# arduinoRGBkaleidoscopeCkt1_v2.net
KiCad netlist of a schematic drawn in EAGLE
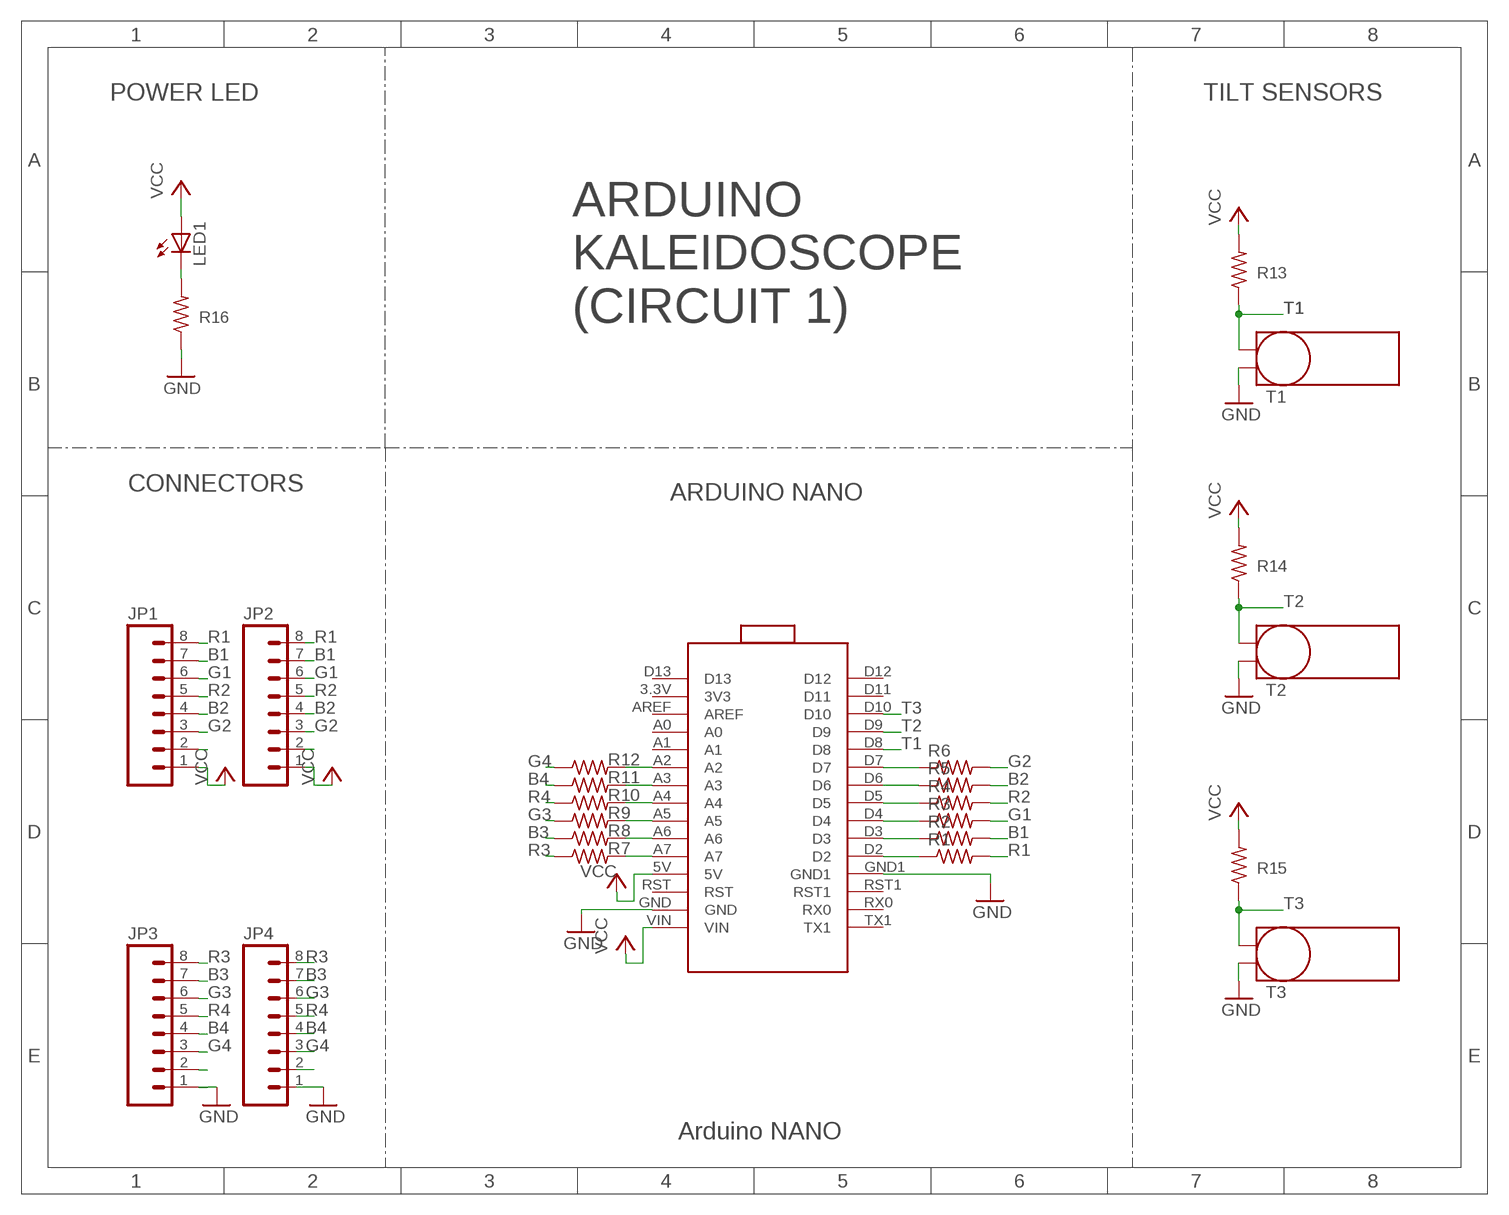
[diagram p0: schematic, sheet 1]

(export (version "E")
  (design (tool "Eeschema 10.0.6"))
  (components
    (comp (ref "JP1")
      (value "M081X08")
      (footprint "eagle-import:1X08")
      (libsource (lib "eagle-import") (part "M081X08"))
    )
    (comp (ref "JP2")
      (value "M081X08")
      (footprint "eagle-import:1X08")
      (libsource (lib "eagle-import") (part "M081X08"))
    )
    (comp (ref "JP3")
      (value "M081X08")
      (footprint "eagle-import:1X08")
      (libsource (lib "eagle-import") (part "M081X08"))
    )
    (comp (ref "JP4")
      (value "M081X08")
      (footprint "eagle-import:1X08")
      (libsource (lib "eagle-import") (part "M081X08"))
    )
    (comp (ref "LED1")
      (value "LED3MM")
      (footprint "eagle-import:LED3MM")
      (libsource (lib "eagle-import") (part "LED3MM"))
    )
    (comp (ref "R1")
      (value "RESISTOR0805")
      (footprint "eagle-import:R0805")
      (libsource (lib "eagle-import") (part "RESISTOR0805"))
    )
    (comp (ref "R2")
      (value "RESISTOR0805")
      (footprint "eagle-import:R0805")
      (libsource (lib "eagle-import") (part "RESISTOR0805"))
    )
    (comp (ref "R3")
      (value "RESISTOR0805")
      (footprint "eagle-import:R0805")
      (libsource (lib "eagle-import") (part "RESISTOR0805"))
    )
    (comp (ref "R4")
      (value "RESISTOR0805")
      (footprint "eagle-import:R0805")
      (libsource (lib "eagle-import") (part "RESISTOR0805"))
    )
    (comp (ref "R5")
      (value "RESISTOR0805")
      (footprint "eagle-import:R0805")
      (libsource (lib "eagle-import") (part "RESISTOR0805"))
    )
    (comp (ref "R6")
      (value "RESISTOR0805")
      (footprint "eagle-import:R0805")
      (libsource (lib "eagle-import") (part "RESISTOR0805"))
    )
    (comp (ref "R7")
      (value "RESISTOR0805")
      (footprint "eagle-import:R0805")
      (libsource (lib "eagle-import") (part "RESISTOR0805"))
    )
    (comp (ref "R8")
      (value "RESISTOR0805")
      (footprint "eagle-import:R0805")
      (libsource (lib "eagle-import") (part "RESISTOR0805"))
    )
    (comp (ref "R9")
      (value "RESISTOR0805")
      (footprint "eagle-import:R0805")
      (libsource (lib "eagle-import") (part "RESISTOR0805"))
    )
    (comp (ref "R10")
      (value "RESISTOR0805")
      (footprint "eagle-import:R0805")
      (libsource (lib "eagle-import") (part "RESISTOR0805"))
    )
    (comp (ref "R11")
      (value "RESISTOR0805")
      (footprint "eagle-import:R0805")
      (libsource (lib "eagle-import") (part "RESISTOR0805"))
    )
    (comp (ref "R12")
      (value "RESISTOR0805")
      (footprint "eagle-import:R0805")
      (libsource (lib "eagle-import") (part "RESISTOR0805"))
    )
    (comp (ref "R13")
      (value "R-US_0204/7")
      (footprint "eagle-import:0204_7")
      (libsource (lib "eagle-import") (part "R-US_0204/7"))
    )
    (comp (ref "R14")
      (value "R-US_0204/7")
      (footprint "eagle-import:0204_7")
      (libsource (lib "eagle-import") (part "R-US_0204/7"))
    )
    (comp (ref "R15")
      (value "R-US_0204/7")
      (footprint "eagle-import:0204_7")
      (libsource (lib "eagle-import") (part "R-US_0204/7"))
    )
    (comp (ref "R16")
      (value "R-US_0204/7")
      (footprint "eagle-import:0204_7")
      (libsource (lib "eagle-import") (part "R-US_0204/7"))
    )
    (comp (ref "T1")
      (value "TILTSENSORE2.5-7")
      (footprint "eagle-import:TILTSENSOR")
      (libsource (lib "eagle-import") (part "TILTSENSORE2.5-7"))
    )
    (comp (ref "T2")
      (value "TILTSENSORE2.5-7")
      (footprint "eagle-import:TILTSENSOR")
      (libsource (lib "eagle-import") (part "TILTSENSORE2.5-7"))
    )
    (comp (ref "T3")
      (value "TILTSENSORE2.5-7")
      (footprint "eagle-import:TILTSENSOR")
      (libsource (lib "eagle-import") (part "TILTSENSORE2.5-7"))
    )
    (comp (ref "U$2")
      (value "NANO")
      (footprint "eagle-import:NANO-2")
      (libsource (lib "eagle-import") (part "NANO"))
    )
  )
  (nets
    (net (code "1") (name "/B1") (class "Default")
      (node (ref "JP1") (pin "7") (pinfunction "7_7") (pintype "passive"))
      (node (ref "JP2") (pin "7") (pinfunction "7_7") (pintype "passive"))
      (node (ref "R2") (pin "2") (pinfunction "2_2") (pintype "passive"))
    )
    (net (code "2") (name "/B2") (class "Default")
      (node (ref "JP1") (pin "4") (pinfunction "4_4") (pintype "passive"))
      (node (ref "JP2") (pin "4") (pinfunction "4_4") (pintype "passive"))
      (node (ref "R5") (pin "2") (pinfunction "2_2") (pintype "passive"))
    )
    (net (code "3") (name "/B3") (class "Default")
      (node (ref "JP3") (pin "7") (pinfunction "7_7") (pintype "passive"))
      (node (ref "JP4") (pin "7") (pinfunction "7_7") (pintype "passive"))
      (node (ref "R8") (pin "1") (pinfunction "1_1") (pintype "passive"))
    )
    (net (code "4") (name "/B4") (class "Default")
      (node (ref "JP3") (pin "4") (pinfunction "4_4") (pintype "passive"))
      (node (ref "JP4") (pin "4") (pinfunction "4_4") (pintype "passive"))
      (node (ref "R11") (pin "1") (pinfunction "1_1") (pintype "passive"))
    )
    (net (code "5") (name "/G1") (class "Default")
      (node (ref "JP1") (pin "6") (pinfunction "6_6") (pintype "passive"))
      (node (ref "JP2") (pin "6") (pinfunction "6_6") (pintype "passive"))
      (node (ref "R3") (pin "2") (pinfunction "2_2") (pintype "passive"))
    )
    (net (code "6") (name "/G2") (class "Default")
      (node (ref "JP1") (pin "3") (pinfunction "3_3") (pintype "passive"))
      (node (ref "JP2") (pin "3") (pinfunction "3_3") (pintype "passive"))
      (node (ref "R6") (pin "2") (pinfunction "2_2") (pintype "passive"))
    )
    (net (code "7") (name "/G3") (class "Default")
      (node (ref "JP3") (pin "6") (pinfunction "6_6") (pintype "passive"))
      (node (ref "JP4") (pin "6") (pinfunction "6_6") (pintype "passive"))
      (node (ref "R9") (pin "1") (pinfunction "1_1") (pintype "passive"))
    )
    (net (code "8") (name "/G4") (class "Default")
      (node (ref "JP3") (pin "3") (pinfunction "3_3") (pintype "passive"))
      (node (ref "JP4") (pin "3") (pinfunction "3_3") (pintype "passive"))
      (node (ref "R12") (pin "1") (pinfunction "1_1") (pintype "passive"))
    )
    (net (code "9") (name "/R1") (class "Default")
      (node (ref "JP1") (pin "8") (pinfunction "8_8") (pintype "passive"))
      (node (ref "JP2") (pin "8") (pinfunction "8_8") (pintype "passive"))
      (node (ref "R1") (pin "2") (pinfunction "2_2") (pintype "passive"))
    )
    (net (code "10") (name "/R2") (class "Default")
      (node (ref "JP1") (pin "5") (pinfunction "5_5") (pintype "passive"))
      (node (ref "JP2") (pin "5") (pinfunction "5_5") (pintype "passive"))
      (node (ref "R4") (pin "2") (pinfunction "2_2") (pintype "passive"))
    )
    (net (code "11") (name "/R3") (class "Default")
      (node (ref "JP3") (pin "8") (pinfunction "8_8") (pintype "passive"))
      (node (ref "JP4") (pin "8") (pinfunction "8_8") (pintype "passive"))
      (node (ref "R7") (pin "1") (pinfunction "1_1") (pintype "passive"))
    )
    (net (code "12") (name "/R4") (class "Default")
      (node (ref "JP3") (pin "5") (pinfunction "5_5") (pintype "passive"))
      (node (ref "JP4") (pin "5") (pinfunction "5_5") (pintype "passive"))
      (node (ref "R10") (pin "1") (pinfunction "1_1") (pintype "passive"))
    )
    (net (code "13") (name "/T1") (class "Default")
      (node (ref "R13") (pin "1") (pinfunction "1_1") (pintype "passive"))
      (node (ref "T1") (pin "+") (pinfunction "+_+") (pintype "passive"))
      (node (ref "U$2") (pin "D8") (pinfunction "D8_D8") (pintype "bidirectional"))
    )
    (net (code "14") (name "/T2") (class "Default")
      (node (ref "R14") (pin "1") (pinfunction "1_1") (pintype "passive"))
      (node (ref "T2") (pin "+") (pinfunction "+_+") (pintype "passive"))
      (node (ref "U$2") (pin "D9") (pinfunction "D9_D9") (pintype "bidirectional"))
    )
    (net (code "15") (name "/T3") (class "Default")
      (node (ref "R15") (pin "1") (pinfunction "1_1") (pintype "passive"))
      (node (ref "T3") (pin "+") (pinfunction "+_+") (pintype "passive"))
      (node (ref "U$2") (pin "D10") (pinfunction "D10_D10") (pintype "bidirectional"))
    )
    (net (code "16") (name "GND") (class "Default")
      (node (ref "JP3") (pin "1") (pinfunction "1_1") (pintype "passive"))
      (node (ref "JP4") (pin "1") (pinfunction "1_1") (pintype "passive"))
      (node (ref "R16") (pin "1") (pinfunction "1_1") (pintype "passive"))
      (node (ref "T1") (pin "-") (pinfunction "-_-") (pintype "passive"))
      (node (ref "T2") (pin "-") (pinfunction "-_-") (pintype "passive"))
      (node (ref "T3") (pin "-") (pinfunction "-_-") (pintype "passive"))
      (node (ref "U$2") (pin "GND") (pinfunction "GND_GND") (pintype "bidirectional"))
      (node (ref "U$2") (pin "GND1") (pinfunction "GND1_GND1") (pintype "bidirectional"))
    )
    (net (code "17") (name "Net-(LED1-C)") (class "Default")
      (node (ref "LED1") (pin "K") (pinfunction "C_K") (pintype "passive"))
      (node (ref "R16") (pin "2") (pinfunction "2_2") (pintype "passive"))
    )
    (net (code "18") (name "Net-(R1-Pad1)") (class "Default")
      (node (ref "R1") (pin "1") (pinfunction "1_1") (pintype "passive"))
      (node (ref "U$2") (pin "D2") (pinfunction "D2_D2") (pintype "bidirectional"))
    )
    (net (code "19") (name "Net-(R2-Pad1)") (class "Default")
      (node (ref "R2") (pin "1") (pinfunction "1_1") (pintype "passive"))
      (node (ref "U$2") (pin "D3") (pinfunction "D3_D3") (pintype "bidirectional"))
    )
    (net (code "20") (name "Net-(R3-Pad1)") (class "Default")
      (node (ref "R3") (pin "1") (pinfunction "1_1") (pintype "passive"))
      (node (ref "U$2") (pin "D4") (pinfunction "D4_D4") (pintype "bidirectional"))
    )
    (net (code "21") (name "Net-(R4-Pad1)") (class "Default")
      (node (ref "R4") (pin "1") (pinfunction "1_1") (pintype "passive"))
      (node (ref "U$2") (pin "D5") (pinfunction "D5_D5") (pintype "bidirectional"))
    )
    (net (code "22") (name "Net-(R5-Pad1)") (class "Default")
      (node (ref "R5") (pin "1") (pinfunction "1_1") (pintype "passive"))
      (node (ref "U$2") (pin "D6") (pinfunction "D6_D6") (pintype "bidirectional"))
    )
    (net (code "23") (name "Net-(R6-Pad1)") (class "Default")
      (node (ref "R6") (pin "1") (pinfunction "1_1") (pintype "passive"))
      (node (ref "U$2") (pin "D7") (pinfunction "D7_D7") (pintype "bidirectional"))
    )
    (net (code "24") (name "Net-(R7-Pad2)") (class "Default")
      (node (ref "R7") (pin "2") (pinfunction "2_2") (pintype "passive"))
      (node (ref "U$2") (pin "A7") (pinfunction "A7_A7") (pintype "bidirectional"))
    )
    (net (code "25") (name "Net-(R8-Pad2)") (class "Default")
      (node (ref "R8") (pin "2") (pinfunction "2_2") (pintype "passive"))
      (node (ref "U$2") (pin "A6") (pinfunction "A6_A6") (pintype "bidirectional"))
    )
    (net (code "26") (name "Net-(R9-Pad2)") (class "Default")
      (node (ref "R9") (pin "2") (pinfunction "2_2") (pintype "passive"))
      (node (ref "U$2") (pin "A5") (pinfunction "A5_A5") (pintype "bidirectional"))
    )
    (net (code "27") (name "Net-(R10-Pad2)") (class "Default")
      (node (ref "R10") (pin "2") (pinfunction "2_2") (pintype "passive"))
      (node (ref "U$2") (pin "A4") (pinfunction "A4_A4") (pintype "bidirectional"))
    )
    (net (code "28") (name "Net-(R11-Pad2)") (class "Default")
      (node (ref "R11") (pin "2") (pinfunction "2_2") (pintype "passive"))
      (node (ref "U$2") (pin "A3") (pinfunction "A3_A3") (pintype "bidirectional"))
    )
    (net (code "29") (name "Net-(R12-Pad2)") (class "Default")
      (node (ref "R12") (pin "2") (pinfunction "2_2") (pintype "passive"))
      (node (ref "U$2") (pin "A2") (pinfunction "A2_A2") (pintype "bidirectional"))
    )
    (net (code "30") (name "VCC") (class "Default")
      (node (ref "JP1") (pin "1") (pinfunction "1_1") (pintype "passive"))
      (node (ref "JP2") (pin "1") (pinfunction "1_1") (pintype "passive"))
      (node (ref "LED1") (pin "A") (pinfunction "A_A") (pintype "passive"))
      (node (ref "R13") (pin "2") (pinfunction "2_2") (pintype "passive"))
      (node (ref "R14") (pin "2") (pinfunction "2_2") (pintype "passive"))
      (node (ref "R15") (pin "2") (pinfunction "2_2") (pintype "passive"))
      (node (ref "U$2") (pin "5V") (pinfunction "5V_5V") (pintype "bidirectional"))
      (node (ref "U$2") (pin "VIN") (pinfunction "VIN_VIN") (pintype "bidirectional"))
    )
    (net (code "31") (name "unconnected-(JP1-Pad2)") (class "Default")
      (node (ref "JP1") (pin "2") (pinfunction "2_2") (pintype "passive"))
    )
    (net (code "32") (name "unconnected-(JP2-Pad2)") (class "Default")
      (node (ref "JP2") (pin "2") (pinfunction "2_2") (pintype "passive"))
    )
    (net (code "33") (name "unconnected-(JP3-Pad2)") (class "Default")
      (node (ref "JP3") (pin "2") (pinfunction "2_2") (pintype "passive"))
    )
    (net (code "34") (name "unconnected-(JP4-Pad2)") (class "Default")
      (node (ref "JP4") (pin "2") (pinfunction "2_2") (pintype "passive"))
    )
    (net (code "35") (name "unconnected-(U$2-3V3-Pad3.3V)") (class "Default")
      (node (ref "U$2") (pin "3.3V") (pinfunction "3V3_3.3V") (pintype "bidirectional"))
    )
    (net (code "36") (name "unconnected-(U$2-PadA0)") (class "Default")
      (node (ref "U$2") (pin "A0") (pinfunction "A0_A0") (pintype "bidirectional"))
    )
    (net (code "37") (name "unconnected-(U$2-PadA1)") (class "Default")
      (node (ref "U$2") (pin "A1") (pinfunction "A1_A1") (pintype "bidirectional"))
    )
    (net (code "38") (name "unconnected-(U$2-PadAREF)") (class "Default")
      (node (ref "U$2") (pin "AREF") (pinfunction "AREF_AREF") (pintype "bidirectional"))
    )
    (net (code "39") (name "unconnected-(U$2-PadD11)") (class "Default")
      (node (ref "U$2") (pin "D11") (pinfunction "D11_D11") (pintype "bidirectional"))
    )
    (net (code "40") (name "unconnected-(U$2-PadD12)") (class "Default")
      (node (ref "U$2") (pin "D12") (pinfunction "D12_D12") (pintype "bidirectional"))
    )
    (net (code "41") (name "unconnected-(U$2-PadD13)") (class "Default")
      (node (ref "U$2") (pin "D13") (pinfunction "D13_D13") (pintype "bidirectional"))
    )
    (net (code "42") (name "unconnected-(U$2-PadRST)") (class "Default")
      (node (ref "U$2") (pin "RST") (pinfunction "RST_RST") (pintype "bidirectional"))
    )
    (net (code "43") (name "unconnected-(U$2-PadRST1)") (class "Default")
      (node (ref "U$2") (pin "RST1") (pinfunction "RST1_RST1") (pintype "bidirectional"))
    )
    (net (code "44") (name "unconnected-(U$2-PadRX0)") (class "Default")
      (node (ref "U$2") (pin "RX0") (pinfunction "RX0_RX0") (pintype "bidirectional"))
    )
    (net (code "45") (name "unconnected-(U$2-PadTX1)") (class "Default")
      (node (ref "U$2") (pin "TX1") (pinfunction "TX1_TX1") (pintype "bidirectional"))
    )
  )
)
